# cpod.net
KiCad netlist of a schematic drawn in EAGLE
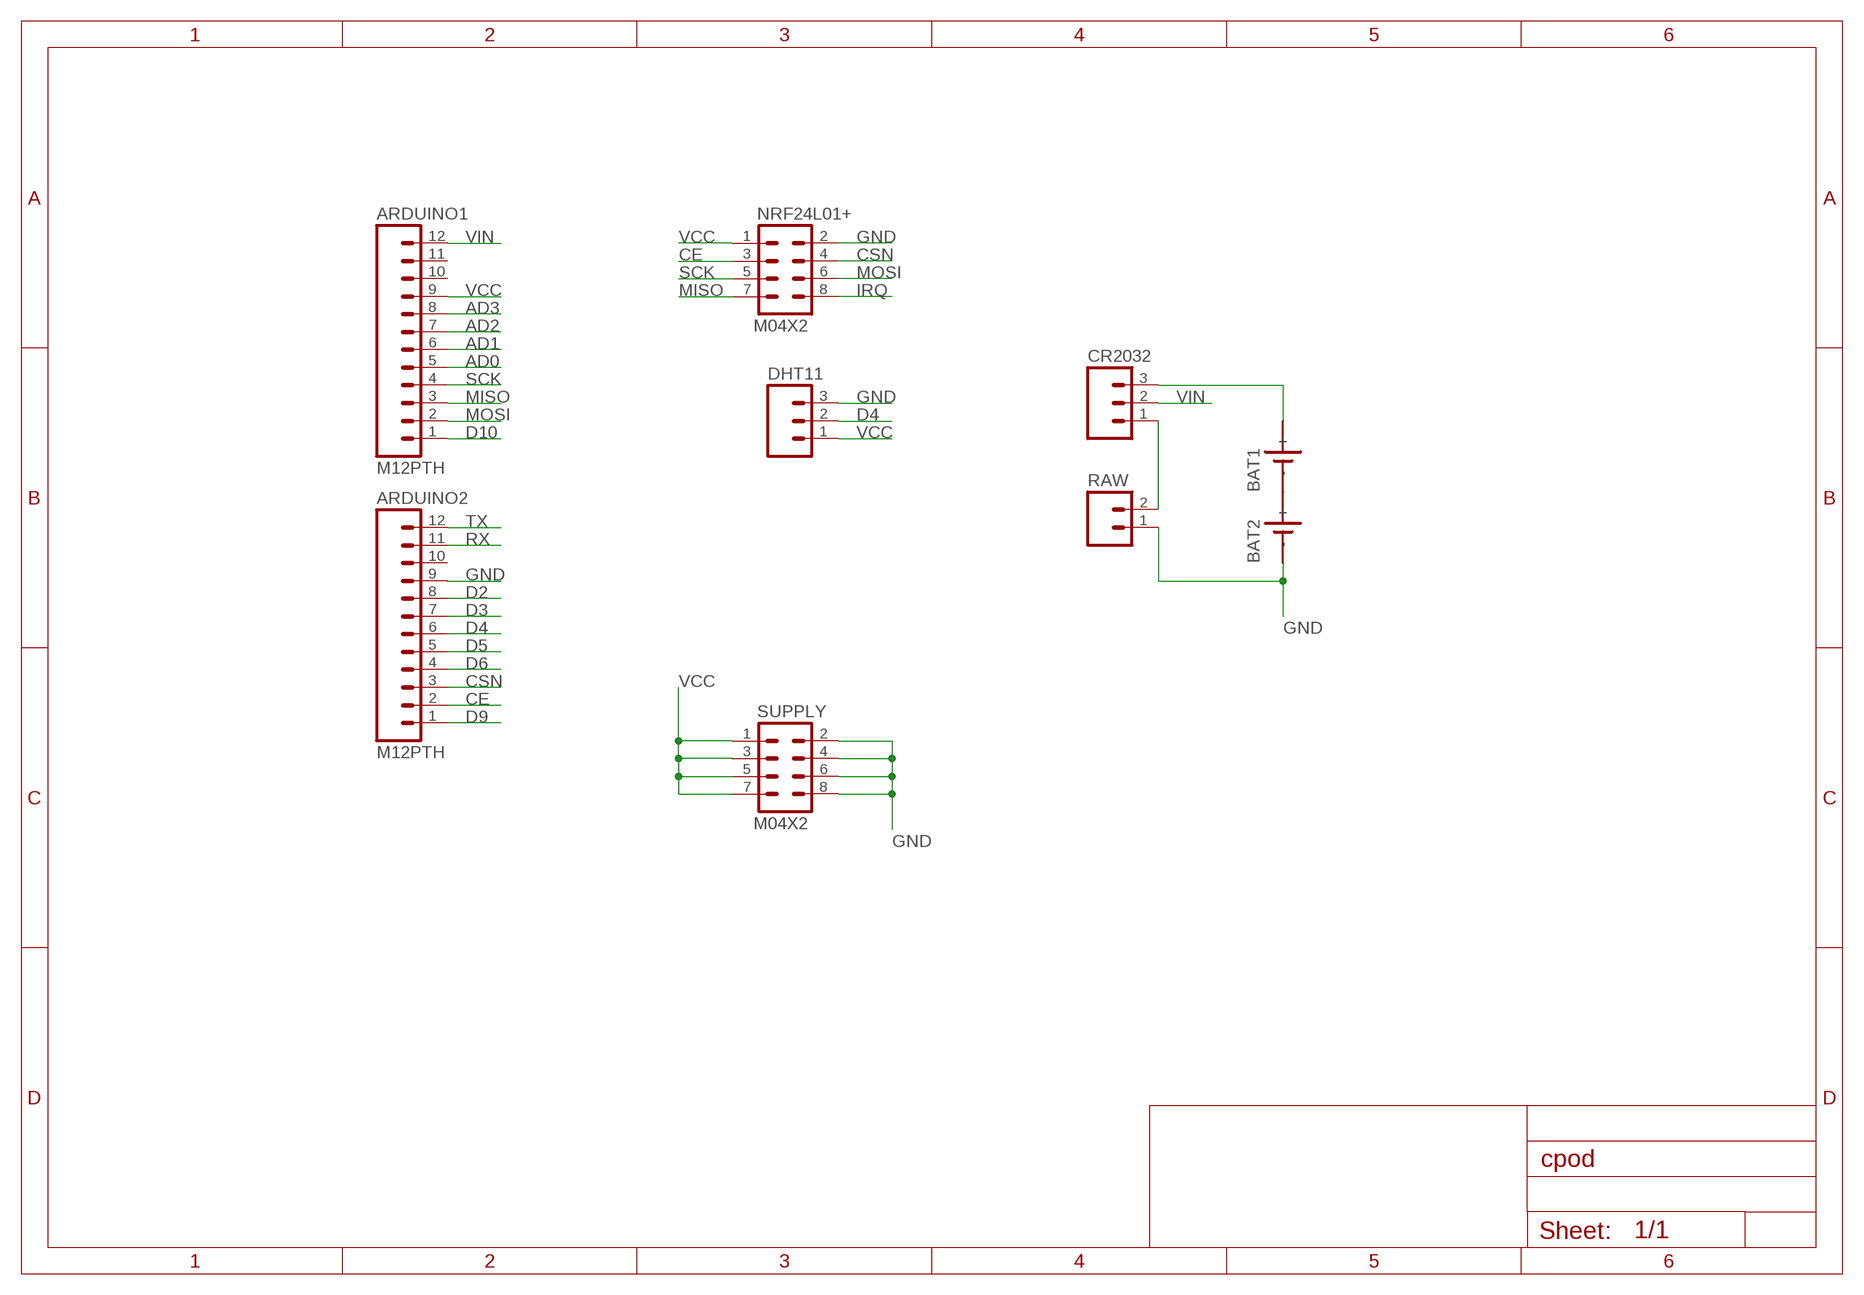
[diagram p0: schematic, sheet 1]

(export (version "E")
  (design (tool "Eeschema 10.0.6"))
  (components
    (comp (ref "ARDUINO1")
      (value "M12PTH")
      (footprint "eagle-import:1X12")
      (libsource (lib "eagle-import") (part "M12PTH"))
    )
    (comp (ref "ARDUINO2")
      (value "M12PTH")
      (footprint "eagle-import:1X12")
      (libsource (lib "eagle-import") (part "M12PTH"))
    )
    (comp (ref "BAT1")
      (value "SN2032")
      (footprint "eagle-import:SN2032")
      (libsource (lib "eagle-import") (part "SN2032"))
    )
    (comp (ref "BAT2")
      (value "SN2032")
      (footprint "eagle-import:SN2032")
      (libsource (lib "eagle-import") (part "SN2032"))
    )
    (comp (ref "CR2032")
      (value "M03PTH")
      (footprint "eagle-import:1X03")
      (libsource (lib "eagle-import") (part "M03PTH"))
    )
    (comp (ref "DHT11")
      (value "M03PTH")
      (footprint "eagle-import:1X03")
      (libsource (lib "eagle-import") (part "M03PTH"))
    )
    (comp (ref "NRF24L01+")
      (value "M04X2")
      (footprint "eagle-import:2X4")
      (libsource (lib "eagle-import") (part "M04X2"))
    )
    (comp (ref "RAW")
      (value "M02PTH")
      (footprint "eagle-import:1X02")
      (libsource (lib "eagle-import") (part "M02PTH"))
    )
    (comp (ref "SUPPLY")
      (value "M04X2")
      (footprint "eagle-import:2X4")
      (libsource (lib "eagle-import") (part "M04X2"))
    )
  )
  (nets
    (net (code "1") (name "/AD0") (class "Default")
      (node (ref "ARDUINO1") (pin "5") (pinfunction "5_5") (pintype "passive"))
    )
    (net (code "2") (name "/AD1") (class "Default")
      (node (ref "ARDUINO1") (pin "6") (pinfunction "6_6") (pintype "passive"))
    )
    (net (code "3") (name "/AD2") (class "Default")
      (node (ref "ARDUINO1") (pin "7") (pinfunction "7_7") (pintype "passive"))
    )
    (net (code "4") (name "/AD3") (class "Default")
      (node (ref "ARDUINO1") (pin "8") (pinfunction "8_8") (pintype "passive"))
    )
    (net (code "5") (name "/CE") (class "Default")
      (node (ref "ARDUINO2") (pin "2") (pinfunction "2_2") (pintype "passive"))
      (node (ref "NRF24L01+") (pin "3") (pinfunction "3_3") (pintype "passive"))
    )
    (net (code "6") (name "/CSN") (class "Default")
      (node (ref "ARDUINO2") (pin "3") (pinfunction "3_3") (pintype "passive"))
      (node (ref "NRF24L01+") (pin "4") (pinfunction "4_4") (pintype "passive"))
    )
    (net (code "7") (name "/D2") (class "Default")
      (node (ref "ARDUINO2") (pin "8") (pinfunction "8_8") (pintype "passive"))
    )
    (net (code "8") (name "/D3") (class "Default")
      (node (ref "ARDUINO2") (pin "7") (pinfunction "7_7") (pintype "passive"))
    )
    (net (code "9") (name "/D4") (class "Default")
      (node (ref "ARDUINO2") (pin "6") (pinfunction "6_6") (pintype "passive"))
      (node (ref "DHT11") (pin "2") (pinfunction "2_2") (pintype "passive"))
    )
    (net (code "10") (name "/D5") (class "Default")
      (node (ref "ARDUINO2") (pin "5") (pinfunction "5_5") (pintype "passive"))
    )
    (net (code "11") (name "/D6") (class "Default")
      (node (ref "ARDUINO2") (pin "4") (pinfunction "4_4") (pintype "passive"))
    )
    (net (code "12") (name "/D9") (class "Default")
      (node (ref "ARDUINO2") (pin "1") (pinfunction "1_1") (pintype "passive"))
    )
    (net (code "13") (name "/D10") (class "Default")
      (node (ref "ARDUINO1") (pin "1") (pinfunction "1_1") (pintype "passive"))
    )
    (net (code "14") (name "/GND") (class "Default")
      (node (ref "ARDUINO2") (pin "9") (pinfunction "9_9") (pintype "passive"))
      (node (ref "BAT2") (pin "-") (pinfunction "-_-") (pintype "passive"))
      (node (ref "DHT11") (pin "3") (pinfunction "3_3") (pintype "passive"))
      (node (ref "NRF24L01+") (pin "2") (pinfunction "2_2") (pintype "passive"))
      (node (ref "RAW") (pin "1") (pinfunction "1_1") (pintype "passive"))
      (node (ref "SUPPLY") (pin "2") (pinfunction "2_2") (pintype "passive"))
      (node (ref "SUPPLY") (pin "4") (pinfunction "4_4") (pintype "passive"))
      (node (ref "SUPPLY") (pin "6") (pinfunction "6_6") (pintype "passive"))
      (node (ref "SUPPLY") (pin "8") (pinfunction "8_8") (pintype "passive"))
    )
    (net (code "15") (name "/IRQ") (class "Default")
      (node (ref "NRF24L01+") (pin "8") (pinfunction "8_8") (pintype "passive"))
    )
    (net (code "16") (name "/MISO") (class "Default")
      (node (ref "ARDUINO1") (pin "3") (pinfunction "3_3") (pintype "passive"))
      (node (ref "NRF24L01+") (pin "7") (pinfunction "7_7") (pintype "passive"))
    )
    (net (code "17") (name "/MOSI") (class "Default")
      (node (ref "ARDUINO1") (pin "2") (pinfunction "2_2") (pintype "passive"))
      (node (ref "NRF24L01+") (pin "6") (pinfunction "6_6") (pintype "passive"))
    )
    (net (code "18") (name "/RX") (class "Default")
      (node (ref "ARDUINO2") (pin "11") (pinfunction "11_11") (pintype "passive"))
    )
    (net (code "19") (name "/SCK") (class "Default")
      (node (ref "ARDUINO1") (pin "4") (pinfunction "4_4") (pintype "passive"))
      (node (ref "NRF24L01+") (pin "5") (pinfunction "5_5") (pintype "passive"))
    )
    (net (code "20") (name "/TX") (class "Default")
      (node (ref "ARDUINO2") (pin "12") (pinfunction "12_12") (pintype "passive"))
    )
    (net (code "21") (name "/VCC") (class "Default")
      (node (ref "ARDUINO1") (pin "9") (pinfunction "9_9") (pintype "passive"))
      (node (ref "DHT11") (pin "1") (pinfunction "1_1") (pintype "passive"))
      (node (ref "NRF24L01+") (pin "1") (pinfunction "1_1") (pintype "passive"))
      (node (ref "SUPPLY") (pin "1") (pinfunction "1_1") (pintype "passive"))
      (node (ref "SUPPLY") (pin "3") (pinfunction "3_3") (pintype "passive"))
      (node (ref "SUPPLY") (pin "5") (pinfunction "5_5") (pintype "passive"))
      (node (ref "SUPPLY") (pin "7") (pinfunction "7_7") (pintype "passive"))
    )
    (net (code "22") (name "/VIN") (class "Default")
      (node (ref "ARDUINO1") (pin "12") (pinfunction "12_12") (pintype "passive"))
      (node (ref "CR2032") (pin "2") (pinfunction "2_2") (pintype "passive"))
    )
    (net (code "23") (name "Net-(BAT1-Pad+)") (class "Default")
      (node (ref "BAT1") (pin "+") (pinfunction "+_+") (pintype "passive"))
      (node (ref "CR2032") (pin "3") (pinfunction "3_3") (pintype "passive"))
    )
    (net (code "24") (name "Net-(BAT1-Pad-)") (class "Default")
      (node (ref "BAT1") (pin "-") (pinfunction "-_-") (pintype "passive"))
      (node (ref "BAT2") (pin "+") (pinfunction "+_+") (pintype "passive"))
    )
    (net (code "25") (name "Net-(CR2032-Pad1)") (class "Default")
      (node (ref "CR2032") (pin "1") (pinfunction "1_1") (pintype "passive"))
      (node (ref "RAW") (pin "2") (pinfunction "2_2") (pintype "passive"))
    )
    (net (code "26") (name "unconnected-(ARDUINO1-Pad10)") (class "Default")
      (node (ref "ARDUINO1") (pin "10") (pinfunction "10_10") (pintype "passive"))
    )
    (net (code "27") (name "unconnected-(ARDUINO1-Pad11)") (class "Default")
      (node (ref "ARDUINO1") (pin "11") (pinfunction "11_11") (pintype "passive"))
    )
    (net (code "28") (name "unconnected-(ARDUINO2-Pad10)") (class "Default")
      (node (ref "ARDUINO2") (pin "10") (pinfunction "10_10") (pintype "passive"))
    )
  )
)
